# jn5168_blk.net
KiCad netlist of a schematic drawn in Altium Designer
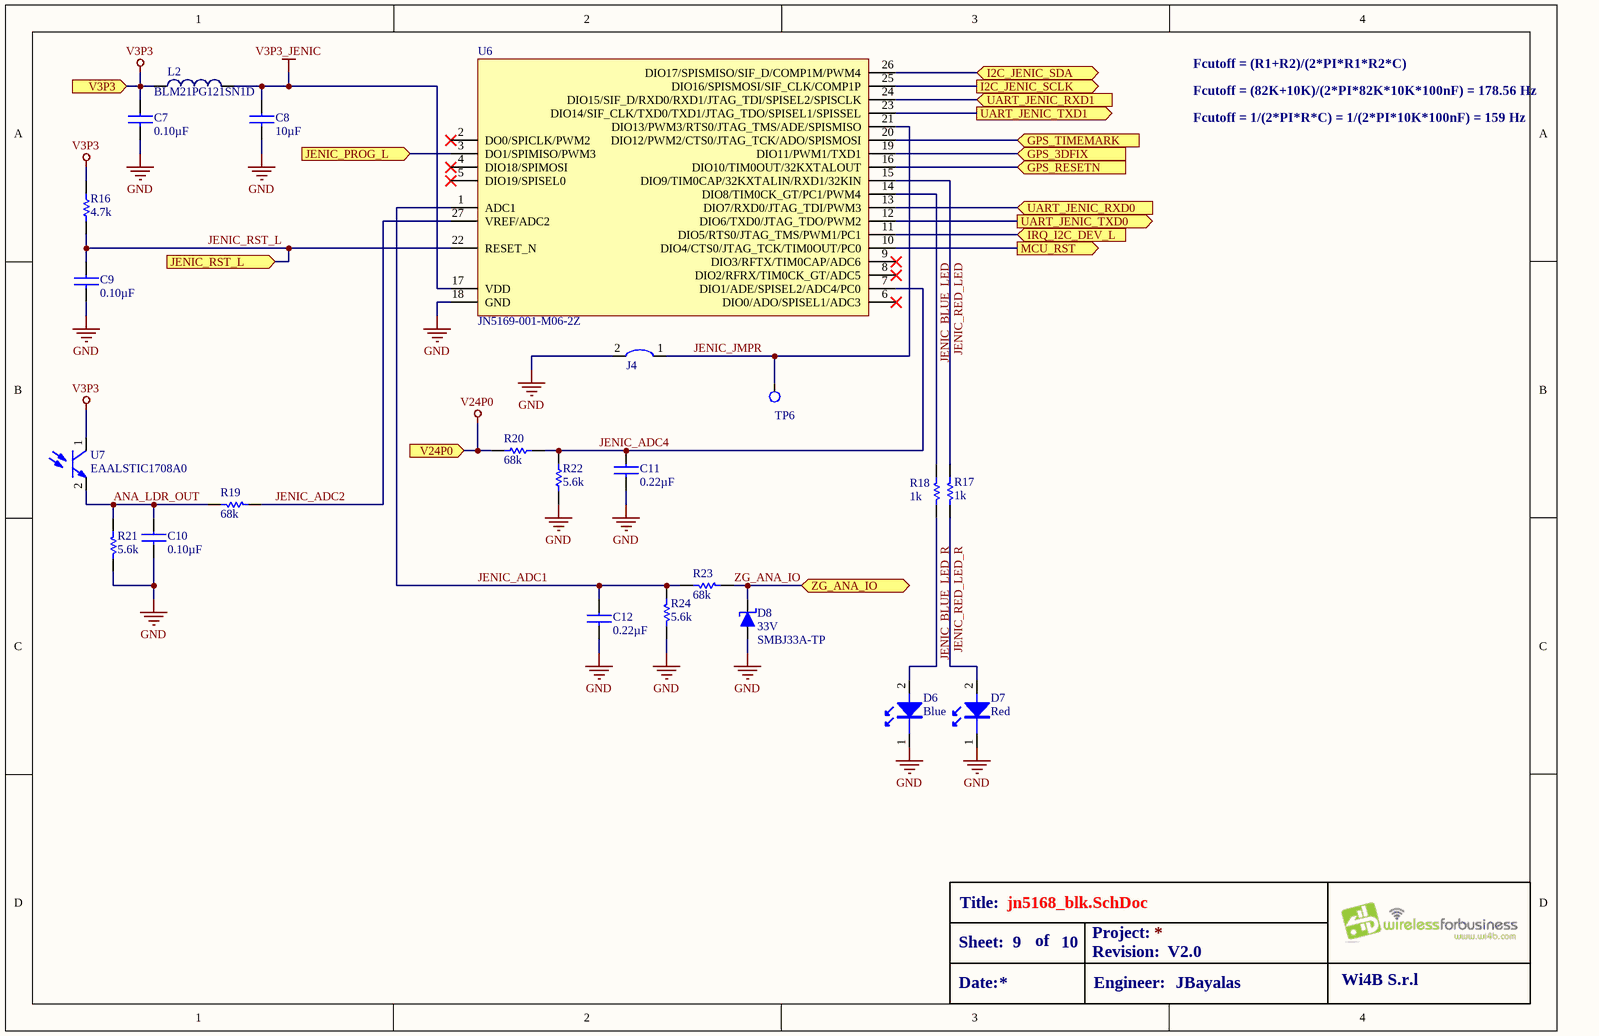
[diagram p0: jn5168_blk.SchDoc]

(export (version "E")
  (design (tool "Eeschema 10.0.6"))
  (components
    (comp (ref "C7")
      (value "0.10µF")
      (footprint "C0402")
      (description "CAP CER 0.1UF 50V X7R 0402")
      (fields (field (name "MPN") "GRM155R71H104ME14D"))
      (libsource (lib "Capacitor") (part "GRM155R71H104ME14D"))
    )
    (comp (ref "C8")
      (value "10µF")
      (footprint "C1206")
      (description "CAP CER 10UF 16V X7R 1206")
      (fields (field (name "MPN") "GRM31CR71C106KAC7L"))
      (libsource (lib "Capacitor") (part "GRM31CR71C106KAC7L"))
    )
    (comp (ref "C9")
      (value "0.10µF")
      (footprint "C0402")
      (description "CAP CER 0.1UF 50V X7R 0402")
      (fields (field (name "MPN") "GRM155R71H104ME14D"))
      (libsource (lib "Capacitor") (part "GRM155R71H104ME14D"))
    )
    (comp (ref "C10")
      (value "0.10µF")
      (footprint "C0402")
      (description "CAP CER 0.1UF 50V X7R 0402")
      (fields (field (name "MPN") "GRM155R71H104ME14D"))
      (libsource (lib "Capacitor") (part "GRM155R71H104ME14D"))
    )
    (comp (ref "C11")
      (value "0.22µF")
      (footprint "C0603")
      (description "CAP CER 0.22UF 50V X7R 0603")
      (fields (field (name "MPN") "GCM188R71H224KA64D"))
      (libsource (lib "Capacitor") (part "GCM188R71H224KA64D"))
    )
    (comp (ref "C12")
      (value "0.22µF")
      (footprint "C0603")
      (description "CAP CER 0.22UF 50V X7R 0603")
      (fields (field (name "MPN") "GCM188R71H224KA64D"))
      (libsource (lib "wiLamp_st") (part "GCM188R71H224KA64D"))
    )
    (comp (ref "D6")
      (value "Blue")
      (footprint "LED0402(BLUE)")
      (description "LED BLUE 0402 SMD")
      (fields (field (name "MPN") "VLMB1500-GS08"))
      (libsource (lib "Diode") (part "VLMB1500-GS08"))
    )
    (comp (ref "D7")
      (value "Red")
      (footprint "LED0402(RED)")
      (description "LED RED 0402 SMD")
      (fields (field (name "MPN") "VLMS1500-GS08"))
      (libsource (lib "Diode") (part "VLMS1500-GS08"))
    )
    (comp (ref "D8")
      (value "SMBJ33A-TP")
      (footprint "DO-214AA, SMB")
      (description "TVS DIODE 33VWM 53.3VC SMB")
      (fields (field (name "RATING") "33V") (field (name "MPN") "SMBJ33A-TP"))
      (libsource (lib "wilamp_st") (part "SMBJ33A-TP"))
    )
    (comp (ref "J4")
      (value "0603 Jumper")
      (footprint "0603 Jumper")
      (libsource (lib "Connector") (part "0603 Jumper"))
    )
    (comp (ref "L2")
      (value "BLM21PG121SN1D")
      (footprint "0805 INDUCTOR")
      (description "FERRITE CHIP 120 OHM 0805")
      (fields (field (name "MPN") "BLM21PG121SN1D"))
      (libsource (lib "Inductor") (part "BLM21PG121SN1D"))
    )
    (comp (ref "R16")
      (value "4.7k")
      (footprint "R0402")
      (description "RES SMD 4.7K OHM 1% 1/10W 0402")
      (fields (field (name "MPN") "MCS04020C4701FE000"))
      (libsource (lib "Res") (part "MCS04020C4701FE000"))
    )
    (comp (ref "R17")
      (value "1k")
      (footprint "R0402")
      (description "RES SMD 1K OHM 1% 1/10W 0402")
      (fields (field (name "MPN") "MCS04020C1001FE000"))
      (libsource (lib "Res") (part "MCS04020C1001FE000"))
    )
    (comp (ref "R18")
      (value "1k")
      (footprint "R0402")
      (description "RES SMD 1K OHM 1% 1/10W 0402")
      (fields (field (name "MPN") "MCS04020C1001FE000"))
      (libsource (lib "Res") (part "MCS04020C1001FE000"))
    )
    (comp (ref "R19")
      (value "68k")
      (footprint "R0603")
      (description "RES SMD 68K OHM 0.1% 1/10W 0603")
      (fields (field (name "MPN") "ERA-3AEB683V"))
      (libsource (lib "Res") (part "ERA-3AEB683V"))
    )
    (comp (ref "R20")
      (value "68k")
      (footprint "R0603")
      (description "RES SMD 68K OHM 0.1% 1/10W 0603")
      (fields (field (name "MPN") "ERA-3AEB683V"))
      (libsource (lib "Res") (part "ERA-3AEB683V"))
    )
    (comp (ref "R21")
      (value "5.6k")
      (footprint "R0603")
      (description "RES SMD 5.6K OHM 0.1% 1/10W 0603")
      (fields (field (name "MPN") "ERA-3AEB562V"))
      (libsource (lib "Res") (part "ERA-3AEB562V"))
    )
    (comp (ref "R22")
      (value "5.6k")
      (footprint "R0603")
      (description "RES SMD 5.6K OHM 0.1% 1/10W 0603")
      (fields (field (name "MPN") "ERA-3AEB562V"))
      (libsource (lib "Res") (part "ERA-3AEB562V"))
    )
    (comp (ref "R23")
      (value "68k")
      (footprint "R0603")
      (description "RES SMD 68K OHM 0.1% 1/10W 0603")
      (fields (field (name "MPN") "ERA-3AEB683V"))
      (libsource (lib "Res") (part "ERA-3AEB683V"))
    )
    (comp (ref "R24")
      (value "5.6k")
      (footprint "R0603")
      (description "RES SMD 5.6K OHM 0.1% 1/10W 0603")
      (fields (field (name "MPN") "ERA-3AEB562V"))
      (libsource (lib "Res") (part "ERA-3AEB562V"))
    )
    (comp (ref "TP6")
      (value "Test Point_2mm")
      (footprint "Test Point 2mm")
      (description "Test Point 2mm")
      (libsource (lib "Miscellaneous") (part "Test Point_2mm"))
    )
    (comp (ref "U6")
      (value "JN5169-001-M06-2Z")
      (footprint "JN5168-001-M06Z")
      (description "JN5169-001-M06-2 ZIGBEE 3.0, ZIG")
      (fields (field (name "MPN") "JN5169-001-M06-2Z"))
      (libsource (lib "Module") (part "JN5169-001-M06-2Z"))
    )
    (comp (ref "U7")
      (value "EAALSTIC1708A0")
      (footprint "EAALSTIC1708A0")
      (description "Ambient Light Sensors Analog Sensor - SMD 630nm")
      (fields (field (name "MPN") "EAALSTIC1708A0"))
      (libsource (lib "IC") (part "EAALSTIC1708A0"))
    )
  )
  (nets
    (net (code "1") (name "/ANA_LDR_OUT") (class "Default")
      (node (ref "C10") (pin "1") (pinfunction "1_1") (pintype "passive"))
      (node (ref "R19") (pin "2") (pinfunction "2_2") (pintype "passive"))
      (node (ref "R21") (pin "2") (pinfunction "2_2") (pintype "passive"))
      (node (ref "U7") (pin "2") (pinfunction "EMITTER_2") (pintype "passive"))
    )
    (net (code "2") (name "/GPS_3DFIX") (class "Default")
      (node (ref "U6") (pin "19") (pinfunction "DIO11/PWM1/TXD1_19") (pintype "passive"))
    )
    (net (code "3") (name "/GPS_RESETN") (class "Default")
      (node (ref "U6") (pin "16") (pinfunction "DIO10/TIM0OUT/32KXTALOUT_16") (pintype "passive"))
    )
    (net (code "4") (name "/GPS_TIMEMARK") (class "Default")
      (node (ref "U6") (pin "20") (pinfunction "DIO12/PWM2/CTS0/JTAG_TCK/ADO/SPISMOSI_20") (pintype "passive"))
    )
    (net (code "5") (name "/I2C_JENIC_SCLK") (class "Default")
      (node (ref "U6") (pin "25") (pinfunction "DIO16/SPISMOSI/SIF_CLK/COMP1P_25") (pintype "passive"))
    )
    (net (code "6") (name "/I2C_JENIC_SDA") (class "Default")
      (node (ref "U6") (pin "26") (pinfunction "DIO17/SPISMISO/SIF_D/COMP1M/PWM4_26") (pintype "passive"))
    )
    (net (code "7") (name "/IRQ_I2C_DEV_L") (class "Default")
      (node (ref "U6") (pin "11") (pinfunction "DIO5/RTS0/JTAG_TMS/PWM1/PC1_11") (pintype "passive"))
    )
    (net (code "8") (name "/JENIC_ADC1") (class "Default")
      (node (ref "C12") (pin "1") (pinfunction "1_1") (pintype "passive"))
      (node (ref "R23") (pin "2") (pinfunction "2_2") (pintype "passive"))
      (node (ref "R24") (pin "2") (pinfunction "2_2") (pintype "passive"))
      (node (ref "U6") (pin "1") (pinfunction "ADC1_1") (pintype "passive"))
    )
    (net (code "9") (name "/JENIC_ADC2") (class "Default")
      (node (ref "R19") (pin "1") (pinfunction "1_1") (pintype "passive"))
      (node (ref "U6") (pin "27") (pinfunction "VREF/ADC2_27") (pintype "passive"))
    )
    (net (code "10") (name "/JENIC_ADC4") (class "Default")
      (node (ref "C11") (pin "1") (pinfunction "1_1") (pintype "passive"))
      (node (ref "R20") (pin "2") (pinfunction "2_2") (pintype "passive"))
      (node (ref "R22") (pin "2") (pinfunction "2_2") (pintype "passive"))
      (node (ref "U6") (pin "7") (pinfunction "DIO1/ADE/SPISEL2/ADC4/PC0_7") (pintype "passive"))
    )
    (net (code "11") (name "/JENIC_BLUE_LED") (class "Default")
      (node (ref "R18") (pin "2") (pinfunction "2_2") (pintype "passive"))
      (node (ref "U6") (pin "14") (pinfunction "DIO8/TIM0CK_GT/PC1/PWM4_14") (pintype "passive"))
    )
    (net (code "12") (name "/JENIC_BLUE_LED_R") (class "Default")
      (node (ref "D6") (pin "2") (pinfunction "2_2") (pintype "passive"))
      (node (ref "R18") (pin "1") (pinfunction "1_1") (pintype "passive"))
    )
    (net (code "13") (name "/JENIC_JMPR") (class "Default")
      (node (ref "J4") (pin "1") (pinfunction "1_1") (pintype "passive"))
      (node (ref "TP6") (pin "1") (pinfunction "1_1") (pintype "passive"))
      (node (ref "U6") (pin "21") (pinfunction "DIO13/PWM3/RTS0/JTAG_TMS/ADE/SPISMISO_21") (pintype "passive"))
    )
    (net (code "14") (name "/JENIC_PROG_L") (class "Default")
      (node (ref "U6") (pin "3") (pinfunction "DO1/SPIMISO/PWM3_3") (pintype "passive"))
    )
    (net (code "15") (name "/JENIC_RED_LED") (class "Default")
      (node (ref "R17") (pin "2") (pinfunction "2_2") (pintype "passive"))
      (node (ref "U6") (pin "15") (pinfunction "DIO9/TIM0CAP/32KXTALIN/RXD1/32KIN_15") (pintype "passive"))
    )
    (net (code "16") (name "/JENIC_RED_LED_R") (class "Default")
      (node (ref "D7") (pin "2") (pinfunction "2_2") (pintype "passive"))
      (node (ref "R17") (pin "1") (pinfunction "1_1") (pintype "passive"))
    )
    (net (code "17") (name "/JENIC_RST_L") (class "Default")
      (node (ref "C9") (pin "1") (pinfunction "1_1") (pintype "passive"))
      (node (ref "R16") (pin "1") (pinfunction "1_1") (pintype "passive"))
      (node (ref "U6") (pin "22") (pinfunction "RESET_N_22") (pintype "passive"))
    )
    (net (code "18") (name "/MCU_RST") (class "Default")
      (node (ref "U6") (pin "10") (pinfunction "DIO4/CTS0/JTAG_TCK/TIM0OUT/PC0_10") (pintype "passive"))
    )
    (net (code "19") (name "/UART_JENIC_RXD0") (class "Default")
      (node (ref "U6") (pin "13") (pinfunction "DIO7/RXD0/JTAG_TDI/PWM3_13") (pintype "passive"))
    )
    (net (code "20") (name "/UART_JENIC_RXD1") (class "Default")
      (node (ref "U6") (pin "24") (pinfunction "DIO15/SIF_D/RXD0/RXD1/JTAG_TDI/SPISEL2/SPISCLK_24") (pintype "passive"))
    )
    (net (code "21") (name "/UART_JENIC_TXD0") (class "Default")
      (node (ref "U6") (pin "12") (pinfunction "DIO6/TXD0/JTAG_TDO/PWM2_12") (pintype "passive"))
    )
    (net (code "22") (name "/UART_JENIC_TXD1") (class "Default")
      (node (ref "U6") (pin "23") (pinfunction "DIO14/SIF_CLK/TXD0/TXD1/JTAG_TDO/SPISEL1/SPISSEL_23") (pintype "passive"))
    )
    (net (code "23") (name "/ZG_ANA_IO") (class "Default")
      (node (ref "D8") (pin "1") (pinfunction "K_1") (pintype "passive"))
      (node (ref "R23") (pin "1") (pinfunction "1_1") (pintype "passive"))
    )
    (net (code "24") (name "GND") (class "Default")
      (node (ref "C10") (pin "2") (pinfunction "2_2") (pintype "passive"))
      (node (ref "C11") (pin "2") (pinfunction "2_2") (pintype "passive"))
      (node (ref "C12") (pin "2") (pinfunction "2_2") (pintype "passive"))
      (node (ref "C7") (pin "2") (pinfunction "2_2") (pintype "passive"))
      (node (ref "C8") (pin "2") (pinfunction "2_2") (pintype "passive"))
      (node (ref "C9") (pin "2") (pinfunction "2_2") (pintype "passive"))
      (node (ref "D6") (pin "1") (pinfunction "1_1") (pintype "passive"))
      (node (ref "D7") (pin "1") (pinfunction "1_1") (pintype "passive"))
      (node (ref "D8") (pin "2") (pinfunction "A_2") (pintype "passive"))
      (node (ref "J4") (pin "2") (pinfunction "2_2") (pintype "passive"))
      (node (ref "R21") (pin "1") (pinfunction "1_1") (pintype "passive"))
      (node (ref "R22") (pin "1") (pinfunction "1_1") (pintype "passive"))
      (node (ref "R24") (pin "1") (pinfunction "1_1") (pintype "passive"))
      (node (ref "U6") (pin "18") (pinfunction "GND_18") (pintype "passive"))
    )
    (net (code "25") (name "V3P3") (class "Default")
      (node (ref "C7") (pin "1") (pinfunction "1_1") (pintype "passive"))
      (node (ref "L2") (pin "2") (pinfunction "2_2") (pintype "passive"))
      (node (ref "R16") (pin "2") (pinfunction "2_2") (pintype "passive"))
      (node (ref "U7") (pin "1") (pinfunction "COLLECTOR_1") (pintype "passive"))
    )
    (net (code "26") (name "V3P3_JENIC") (class "Default")
      (node (ref "C8") (pin "1") (pinfunction "1_1") (pintype "passive"))
      (node (ref "L2") (pin "1") (pinfunction "1_1") (pintype "passive"))
      (node (ref "U6") (pin "17") (pinfunction "VDD_17") (pintype "passive"))
    )
    (net (code "27") (name "V24P0") (class "Default")
      (node (ref "R20") (pin "1") (pinfunction "1_1") (pintype "passive"))
    )
    (net (code "28") (name "unconnected-(U6-DIO0{slash}ADO{slash}SPISEL1{slash}ADC3-Pad6)") (class "Default")
      (node (ref "U6") (pin "6") (pinfunction "DIO0/ADO/SPISEL1/ADC3_6") (pintype "passive+no_connect"))
    )
    (net (code "29") (name "unconnected-(U6-DIO2{slash}RFRX{slash}TIM0CK_GT{slash}ADC5-Pad8)") (class "Default")
      (node (ref "U6") (pin "8") (pinfunction "DIO2/RFRX/TIM0CK_GT/ADC5_8") (pintype "passive+no_connect"))
    )
    (net (code "30") (name "unconnected-(U6-DIO3{slash}RFTX{slash}TIM0CAP{slash}ADC6-Pad9)") (class "Default")
      (node (ref "U6") (pin "9") (pinfunction "DIO3/RFTX/TIM0CAP/ADC6_9") (pintype "passive+no_connect"))
    )
    (net (code "31") (name "unconnected-(U6-DIO18{slash}SPIMOSI-Pad4)") (class "Default")
      (node (ref "U6") (pin "4") (pinfunction "DIO18/SPIMOSI_4") (pintype "passive+no_connect"))
    )
    (net (code "32") (name "unconnected-(U6-DIO19{slash}SPISEL0-Pad5)") (class "Default")
      (node (ref "U6") (pin "5") (pinfunction "DIO19/SPISEL0_5") (pintype "passive+no_connect"))
    )
    (net (code "33") (name "unconnected-(U6-DO0{slash}SPICLK{slash}PWM2-Pad2)") (class "Default")
      (node (ref "U6") (pin "2") (pinfunction "DO0/SPICLK/PWM2_2") (pintype "passive+no_connect"))
    )
  )
)
